# ftdifriend.net
KiCad netlist of a schematic drawn in EAGLE
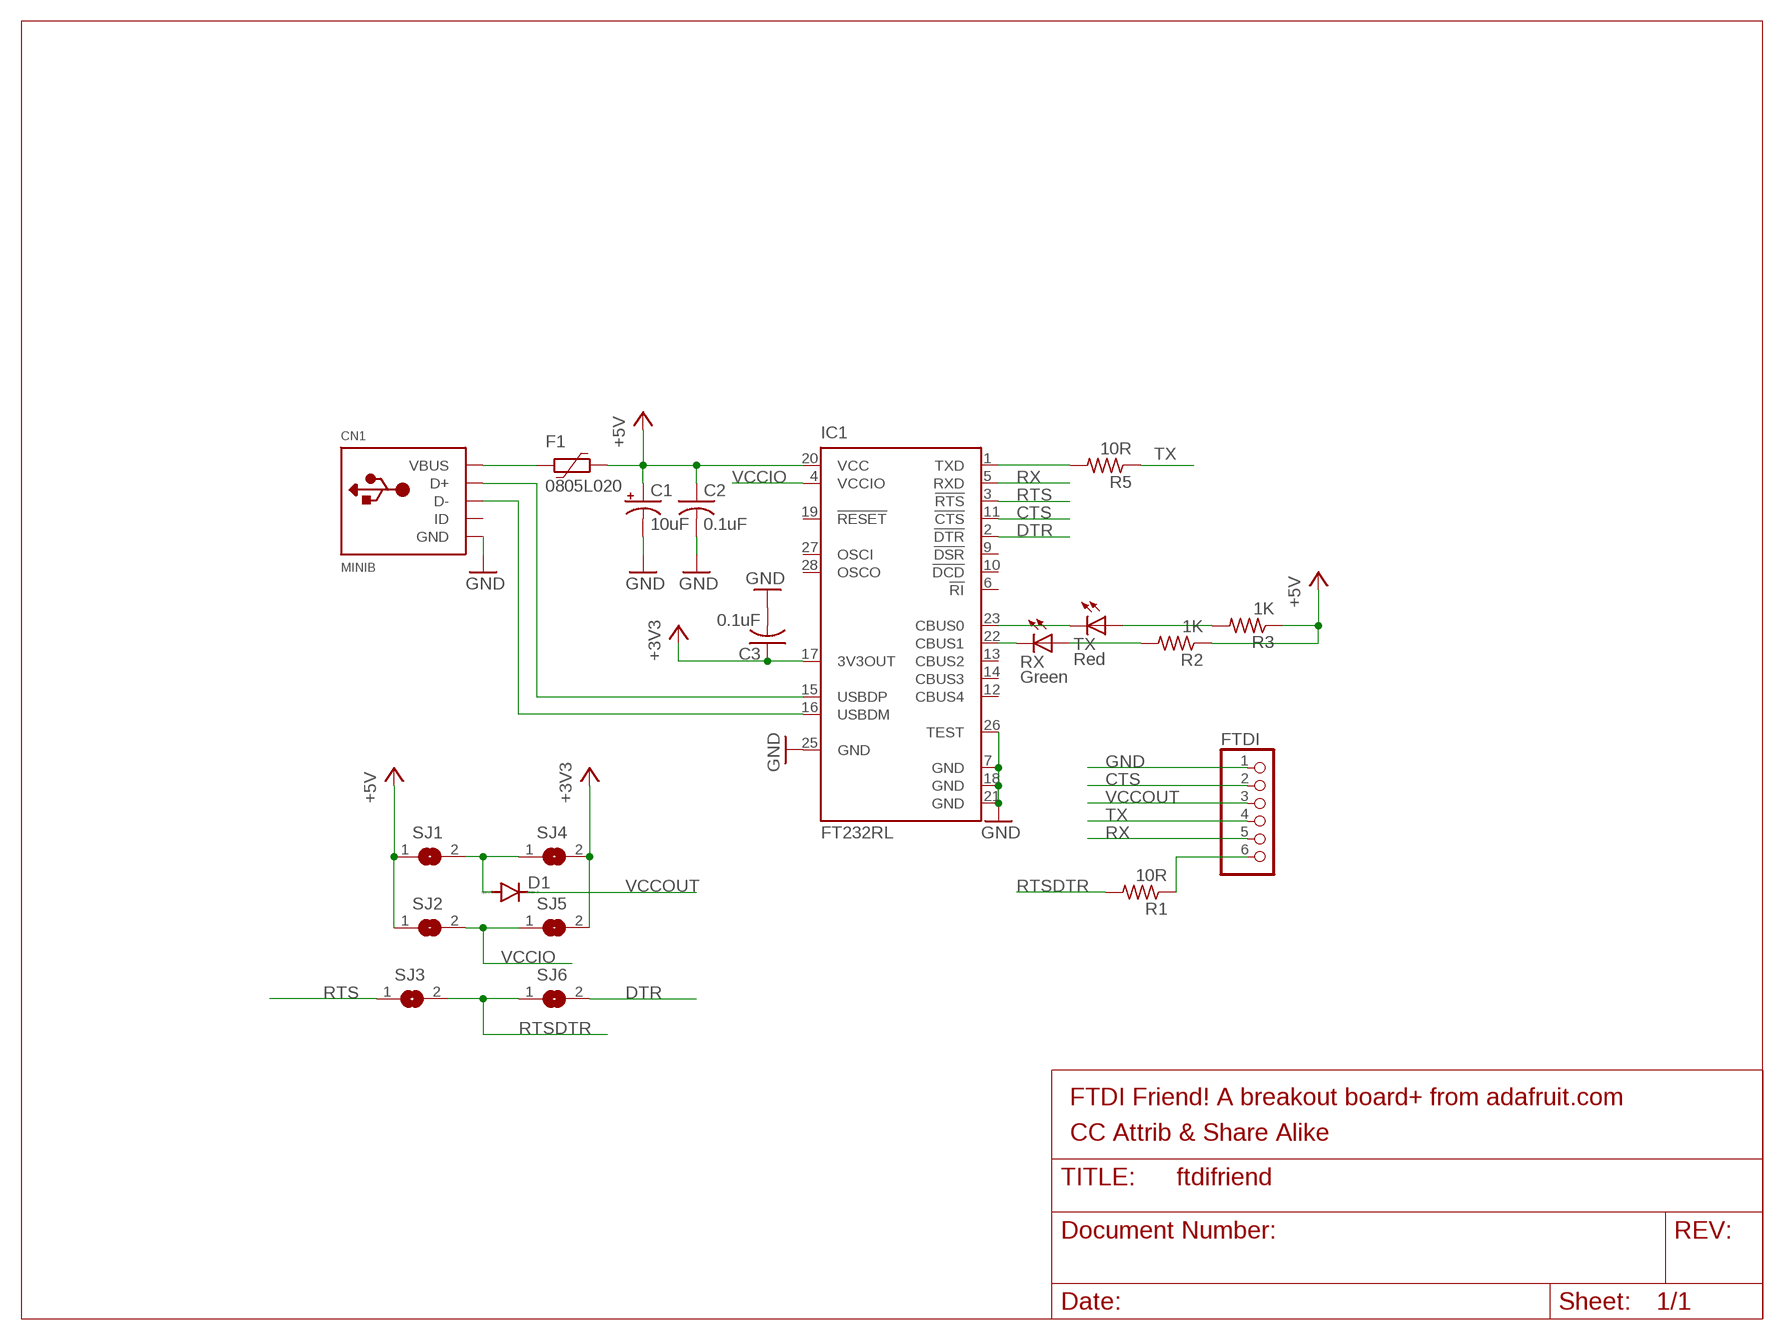
[diagram p0: schematic, sheet 1]

(export (version "E")
  (design (tool "Eeschema 10.0.6"))
  (components
    (comp (ref "C1")
      (value "10uF")
      (footprint "eagle-import:A_3216-18R")
      (libsource (lib "eagle-import") (part "CPOL-USA/3216-18R"))
    )
    (comp (ref "C2")
      (value "0.1uF")
      (footprint "eagle-import:C0805K")
      (libsource (lib "eagle-import") (part "C-USC0805K"))
    )
    (comp (ref "C3")
      (value "0.1uF")
      (footprint "eagle-import:C0805K")
      (libsource (lib "eagle-import") (part "C-USC0805K"))
    )
    (comp (ref "CN1")
      (value "MINIB")
      (footprint "eagle-import:USB-MINIB")
      (libsource (lib "eagle-import") (part "USBMINIB"))
    )
    (comp (ref "D1")
      (value "CUS10F30")
      (footprint "eagle-import:SOD323-W")
      (libsource (lib "eagle-import") (part "DIODE-SOD323-W"))
    )
    (comp (ref "F1")
      (value "0805L020")
      (footprint "eagle-import:0805L")
      (fields (field (name "MF") "Littelfuse"))
      (libsource (lib "eagle-import") (part "?0805L020"))
    )
    (comp (ref "FTDI")
      (value "PINHD-1X6CB")
      (footprint "eagle-import:1X06-CLEANBIG")
      (libsource (lib "eagle-import") (part "PINHD-1X6CB"))
    )
    (comp (ref "IC1")
      (value "FT232RL")
      (footprint "eagle-import:SSOP28")
      (libsource (lib "eagle-import") (part "FT232RL"))
    )
    (comp (ref "R1")
      (value "10R")
      (footprint "eagle-import:R0805")
      (libsource (lib "eagle-import") (part "R-US_R0805"))
    )
    (comp (ref "R2")
      (value "1K")
      (footprint "eagle-import:R0805")
      (libsource (lib "eagle-import") (part "R-US_R0805"))
    )
    (comp (ref "R3")
      (value "1K")
      (footprint "eagle-import:R0805")
      (libsource (lib "eagle-import") (part "R-US_R0805"))
    )
    (comp (ref "R5")
      (value "10R")
      (footprint "eagle-import:R0805")
      (libsource (lib "eagle-import") (part "R-US_R0805"))
    )
    (comp (ref "RX")
      (value "Green")
      (footprint "eagle-import:CHIP-LED0805")
      (libsource (lib "eagle-import") (part "LEDCHIP-LED0805"))
    )
    (comp (ref "SJ1") (value "SJ") (footprint "eagle-import:SJ") (libsource (lib "eagle-import") (part "SJ")))
    (comp (ref "SJ2") (value "SJ") (footprint "eagle-import:SJ") (libsource (lib "eagle-import") (part "SJ")))
    (comp (ref "SJ3") (value "SJ") (footprint "eagle-import:SJ") (libsource (lib "eagle-import") (part "SJ")))
    (comp (ref "SJ4") (value "SJ") (footprint "eagle-import:SJ") (libsource (lib "eagle-import") (part "SJ")))
    (comp (ref "SJ5") (value "SJ") (footprint "eagle-import:SJ") (libsource (lib "eagle-import") (part "SJ")))
    (comp (ref "SJ6") (value "SJ") (footprint "eagle-import:SJ") (libsource (lib "eagle-import") (part "SJ")))
    (comp (ref "TX")
      (value "Red")
      (footprint "eagle-import:CHIP-LED0805")
      (libsource (lib "eagle-import") (part "LEDCHIP-LED0805"))
    )
  )
  (nets
    (net (code "1") (name "+3V3") (class "Default")
      (node (ref "C3") (pin "1") (pinfunction "1_1") (pintype "passive"))
      (node (ref "IC1") (pin "17") (pinfunction "3V3OUT_17") (pintype "input"))
      (node (ref "SJ4") (pin "2") (pinfunction "2_2") (pintype "passive"))
      (node (ref "SJ5") (pin "2") (pinfunction "2_2") (pintype "passive"))
    )
    (net (code "2") (name "+5V") (class "Default")
      (node (ref "C1") (pin "+") (pinfunction "+_+") (pintype "passive"))
      (node (ref "C2") (pin "1") (pinfunction "1_1") (pintype "passive"))
      (node (ref "F1") (pin "1") (pinfunction "1_1") (pintype "passive"))
      (node (ref "IC1") (pin "20") (pinfunction "VCC_20") (pintype "input"))
      (node (ref "R2") (pin "1") (pinfunction "1_1") (pintype "passive"))
      (node (ref "R3") (pin "1") (pinfunction "1_1") (pintype "passive"))
      (node (ref "SJ1") (pin "1") (pinfunction "1_1") (pintype "passive"))
      (node (ref "SJ2") (pin "1") (pinfunction "1_1") (pintype "passive"))
    )
    (net (code "3") (name "/CTS") (class "Default")
      (node (ref "FTDI") (pin "2") (pinfunction "2_2") (pintype "passive"))
      (node (ref "IC1") (pin "11") (pinfunction "~{CTS}_11") (pintype "input"))
    )
    (net (code "4") (name "/DTR") (class "Default")
      (node (ref "IC1") (pin "2") (pinfunction "~{DTR}_2") (pintype "input"))
      (node (ref "SJ6") (pin "2") (pinfunction "2_2") (pintype "passive"))
    )
    (net (code "5") (name "/RTS") (class "Default")
      (node (ref "IC1") (pin "3") (pinfunction "~{RTS}_3") (pintype "input"))
      (node (ref "SJ3") (pin "1") (pinfunction "1_1") (pintype "passive"))
    )
    (net (code "6") (name "/RTSDTR") (class "Default")
      (node (ref "R1") (pin "2") (pinfunction "2_2") (pintype "passive"))
      (node (ref "SJ3") (pin "2") (pinfunction "2_2") (pintype "passive"))
      (node (ref "SJ6") (pin "1") (pinfunction "1_1") (pintype "passive"))
    )
    (net (code "7") (name "/RX") (class "Default")
      (node (ref "FTDI") (pin "5") (pinfunction "5_5") (pintype "passive"))
      (node (ref "IC1") (pin "5") (pinfunction "RXD_5") (pintype "input"))
    )
    (net (code "8") (name "/TX") (class "Default")
      (node (ref "FTDI") (pin "4") (pinfunction "4_4") (pintype "passive"))
      (node (ref "R5") (pin "1") (pinfunction "1_1") (pintype "passive"))
    )
    (net (code "9") (name "/VCCIO") (class "Default")
      (node (ref "IC1") (pin "4") (pinfunction "VCCIO_4") (pintype "input"))
      (node (ref "SJ2") (pin "2") (pinfunction "2_2") (pintype "passive"))
      (node (ref "SJ5") (pin "1") (pinfunction "1_1") (pintype "passive"))
    )
    (net (code "10") (name "/VCCOUT") (class "Default")
      (node (ref "D1") (pin "C") (pinfunction "C_C") (pintype "passive"))
      (node (ref "FTDI") (pin "3") (pinfunction "3_3") (pintype "passive"))
    )
    (net (code "11") (name "GND") (class "Default")
      (node (ref "C1") (pin "-") (pinfunction "-_-") (pintype "passive"))
      (node (ref "C2") (pin "2") (pinfunction "2_2") (pintype "passive"))
      (node (ref "C3") (pin "2") (pinfunction "2_2") (pintype "passive"))
      (node (ref "CN1") (pin "GND") (pinfunction "GND_GND") (pintype "power_in"))
      (node (ref "FTDI") (pin "1") (pinfunction "1_1") (pintype "passive"))
      (node (ref "IC1") (pin "18") (pinfunction "GND_18") (pintype "input"))
      (node (ref "IC1") (pin "21") (pinfunction "GND_21") (pintype "input"))
      (node (ref "IC1") (pin "25") (pinfunction "GND_25") (pintype "input"))
      (node (ref "IC1") (pin "26") (pinfunction "TEST_26") (pintype "input"))
      (node (ref "IC1") (pin "7") (pinfunction "GND_7") (pintype "input"))
    )
    (net (code "12") (name "Net-(CN1-PadVBUS)") (class "Default")
      (node (ref "CN1") (pin "VBUS") (pinfunction "VBUS_VBUS") (pintype "power_in"))
      (node (ref "F1") (pin "2") (pinfunction "2_2") (pintype "passive"))
    )
    (net (code "13") (name "Net-(D1-PadA)") (class "Default")
      (node (ref "D1") (pin "A") (pinfunction "A_A") (pintype "passive"))
      (node (ref "SJ1") (pin "2") (pinfunction "2_2") (pintype "passive"))
      (node (ref "SJ4") (pin "1") (pinfunction "1_1") (pintype "passive"))
    )
    (net (code "14") (name "Net-(FTDI-Pad6)") (class "Default")
      (node (ref "FTDI") (pin "6") (pinfunction "6_6") (pintype "passive"))
      (node (ref "R1") (pin "1") (pinfunction "1_1") (pintype "passive"))
    )
    (net (code "15") (name "Net-(IC1-CBUS0)") (class "Default")
      (node (ref "IC1") (pin "23") (pinfunction "CBUS0_23") (pintype "input"))
      (node (ref "TX") (pin "C") (pinfunction "C_C") (pintype "passive"))
    )
    (net (code "16") (name "Net-(IC1-CBUS1)") (class "Default")
      (node (ref "IC1") (pin "22") (pinfunction "CBUS1_22") (pintype "input"))
      (node (ref "RX") (pin "C") (pinfunction "C_C") (pintype "passive"))
    )
    (net (code "17") (name "Net-(IC1-TXD)") (class "Default")
      (node (ref "IC1") (pin "1") (pinfunction "TXD_1") (pintype "input"))
      (node (ref "R5") (pin "2") (pinfunction "2_2") (pintype "passive"))
    )
    (net (code "18") (name "Net-(IC1-USBDM)") (class "Default")
      (node (ref "CN1") (pin "D-") (pinfunction "D-_D-") (pintype "bidirectional"))
      (node (ref "IC1") (pin "16") (pinfunction "USBDM_16") (pintype "input"))
    )
    (net (code "19") (name "Net-(IC1-USBDP)") (class "Default")
      (node (ref "CN1") (pin "D+") (pinfunction "D+_D+") (pintype "bidirectional"))
      (node (ref "IC1") (pin "15") (pinfunction "USBDP_15") (pintype "input"))
    )
    (net (code "20") (name "Net-(R2-Pad2)") (class "Default")
      (node (ref "R2") (pin "2") (pinfunction "2_2") (pintype "passive"))
      (node (ref "RX") (pin "A") (pinfunction "A_A") (pintype "passive"))
    )
    (net (code "21") (name "Net-(R3-Pad2)") (class "Default")
      (node (ref "R3") (pin "2") (pinfunction "2_2") (pintype "passive"))
      (node (ref "TX") (pin "A") (pinfunction "A_A") (pintype "passive"))
    )
    (net (code "22") (name "unconnected-(CN1-PadID)") (class "Default")
      (node (ref "CN1") (pin "ID") (pinfunction "ID_ID") (pintype "bidirectional"))
    )
    (net (code "23") (name "unconnected-(IC1-CBUS2-Pad13)") (class "Default")
      (node (ref "IC1") (pin "13") (pinfunction "CBUS2_13") (pintype "input"))
    )
    (net (code "24") (name "unconnected-(IC1-CBUS3-Pad14)") (class "Default")
      (node (ref "IC1") (pin "14") (pinfunction "CBUS3_14") (pintype "input"))
    )
    (net (code "25") (name "unconnected-(IC1-CBUS4-Pad12)") (class "Default")
      (node (ref "IC1") (pin "12") (pinfunction "CBUS4_12") (pintype "input"))
    )
    (net (code "26") (name "unconnected-(IC1-OSCI-Pad27)") (class "Default")
      (node (ref "IC1") (pin "27") (pinfunction "OSCI_27") (pintype "input"))
    )
    (net (code "27") (name "unconnected-(IC1-OSCO-Pad28)") (class "Default")
      (node (ref "IC1") (pin "28") (pinfunction "OSCO_28") (pintype "input"))
    )
    (net (code "28") (name "unconnected-(IC1-~{DCD}-Pad10)") (class "Default")
      (node (ref "IC1") (pin "10") (pinfunction "~{DCD}_10") (pintype "input"))
    )
    (net (code "29") (name "unconnected-(IC1-~{DSR}-Pad9)") (class "Default")
      (node (ref "IC1") (pin "9") (pinfunction "~{DSR}_9") (pintype "input"))
    )
    (net (code "30") (name "unconnected-(IC1-~{RESET}-Pad19)") (class "Default")
      (node (ref "IC1") (pin "19") (pinfunction "~{RESET}_19") (pintype "input"))
    )
    (net (code "31") (name "unconnected-(IC1-~{RI}-Pad6)") (class "Default")
      (node (ref "IC1") (pin "6") (pinfunction "~{RI}_6") (pintype "input"))
    )
  )
)
